# SHIELD_PROMINI.net
KiCad netlist of a schematic drawn in EAGLE
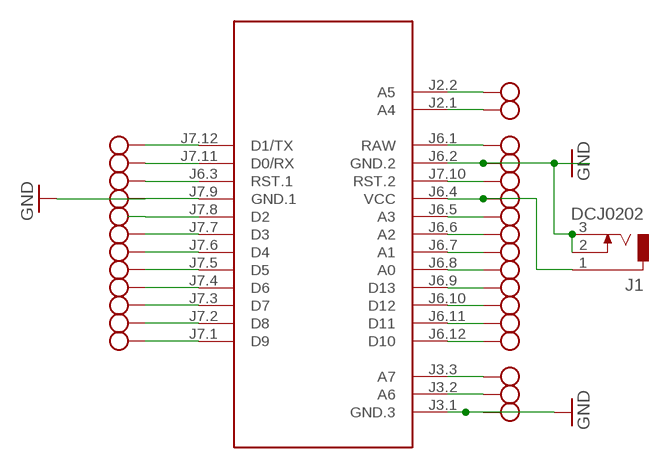
[diagram p0: schematic, sheet 1]

(export (version "E")
  (design (tool "Eeschema 10.0.6"))
  (components
    (comp (ref "J1")
      (value "DCJ0202")
      (footprint "eagle-import:DCJ0202")
      (libsource (lib "eagle-import") (part "DCJ0202"))
    )
    (comp (ref "M1")
      (value "ARDUINO-PRO-MINI-5.0V#NP")
      (footprint "eagle-import:ARDUINO-PRO-MINI#NP")
      (libsource (lib "eagle-import") (part "ARDUINO-PRO-MINI-#NP5.0V"))
    )
    (comp (ref "X1")
      (value "AK300/12")
      (footprint "eagle-import:AK300_12")
      (libsource (lib "eagle-import") (part "AK300/12"))
    )
    (comp (ref "X2")
      (value "AK300/12")
      (footprint "eagle-import:AK300_12")
      (libsource (lib "eagle-import") (part "AK300/12"))
    )
    (comp (ref "X3")
      (value "AK300/5")
      (footprint "eagle-import:AK300_5")
      (libsource (lib "eagle-import") (part "AK300/5"))
    )
  )
  (nets
    (net (code "1") (name "GND") (class "Default")
      (node (ref "J1") (pin "2") (pinfunction "2_2") (pintype "passive"))
      (node (ref "J1") (pin "3") (pinfunction "3_3") (pintype "passive"))
      (node (ref "M1") (pin "J3.1") (pinfunction "GND.3_J3.1") (pintype "bidirectional"))
      (node (ref "M1") (pin "J6.2") (pinfunction "GND.2_J6.2") (pintype "power_in"))
      (node (ref "M1") (pin "J7.9") (pinfunction "GND.1_J7.9") (pintype "power_in"))
      (node (ref "X1") (pin "9") (pinfunction "KL_9") (pintype "passive"))
      (node (ref "X2") (pin "2") (pinfunction "KL_2") (pintype "passive"))
      (node (ref "X3") (pin "3") (pinfunction "KL_3") (pintype "passive"))
    )
    (net (code "2") (name "Net-(M1-A0)") (class "Default")
      (node (ref "M1") (pin "J6.8") (pinfunction "A0_J6.8") (pintype "bidirectional"))
      (node (ref "X2") (pin "8") (pinfunction "KL_8") (pintype "passive"))
    )
    (net (code "3") (name "Net-(M1-A1)") (class "Default")
      (node (ref "M1") (pin "J6.7") (pinfunction "A1_J6.7") (pintype "bidirectional"))
      (node (ref "X2") (pin "7") (pinfunction "KL_7") (pintype "passive"))
    )
    (net (code "4") (name "Net-(M1-A2)") (class "Default")
      (node (ref "M1") (pin "J6.6") (pinfunction "A2_J6.6") (pintype "bidirectional"))
      (node (ref "X2") (pin "6") (pinfunction "KL_6") (pintype "passive"))
    )
    (net (code "5") (name "Net-(M1-A3)") (class "Default")
      (node (ref "M1") (pin "J6.5") (pinfunction "A3_J6.5") (pintype "bidirectional"))
      (node (ref "X2") (pin "5") (pinfunction "KL_5") (pintype "passive"))
    )
    (net (code "6") (name "Net-(M1-A4)") (class "Default")
      (node (ref "M1") (pin "J2.1") (pinfunction "A4_J2.1") (pintype "bidirectional"))
      (node (ref "X3") (pin "4") (pinfunction "KL_4") (pintype "passive"))
    )
    (net (code "7") (name "Net-(M1-A5)") (class "Default")
      (node (ref "M1") (pin "J2.2") (pinfunction "A5_J2.2") (pintype "bidirectional"))
      (node (ref "X3") (pin "5") (pinfunction "KL_5") (pintype "passive"))
    )
    (net (code "8") (name "Net-(M1-A6)") (class "Default")
      (node (ref "M1") (pin "J3.2") (pinfunction "A6_J3.2") (pintype "bidirectional"))
      (node (ref "X3") (pin "2") (pinfunction "KL_2") (pintype "passive"))
    )
    (net (code "9") (name "Net-(M1-A7)") (class "Default")
      (node (ref "M1") (pin "J3.3") (pinfunction "A7_J3.3") (pintype "bidirectional"))
      (node (ref "X3") (pin "1") (pinfunction "KL_1") (pintype "passive"))
    )
    (net (code "10") (name "Net-(M1-D0{slash}RX)") (class "Default")
      (node (ref "M1") (pin "J7.11") (pinfunction "D0/RX_J7.11") (pintype "bidirectional"))
      (node (ref "X1") (pin "11") (pinfunction "KL_11") (pintype "passive"))
    )
    (net (code "11") (name "Net-(M1-D1{slash}TX)") (class "Default")
      (node (ref "M1") (pin "J7.12") (pinfunction "D1/TX_J7.12") (pintype "bidirectional"))
      (node (ref "X1") (pin "12") (pinfunction "KL_12") (pintype "passive"))
    )
    (net (code "12") (name "Net-(M1-D2)") (class "Default")
      (node (ref "M1") (pin "J7.8") (pinfunction "D2_J7.8") (pintype "bidirectional"))
      (node (ref "X1") (pin "8") (pinfunction "KL_8") (pintype "passive"))
    )
    (net (code "13") (name "Net-(M1-D3)") (class "Default")
      (node (ref "M1") (pin "J7.7") (pinfunction "D3_J7.7") (pintype "bidirectional"))
      (node (ref "X1") (pin "7") (pinfunction "KL_7") (pintype "passive"))
    )
    (net (code "14") (name "Net-(M1-D4)") (class "Default")
      (node (ref "M1") (pin "J7.6") (pinfunction "D4_J7.6") (pintype "bidirectional"))
      (node (ref "X1") (pin "6") (pinfunction "KL_6") (pintype "passive"))
    )
    (net (code "15") (name "Net-(M1-D5)") (class "Default")
      (node (ref "M1") (pin "J7.5") (pinfunction "D5_J7.5") (pintype "bidirectional"))
      (node (ref "X1") (pin "5") (pinfunction "KL_5") (pintype "passive"))
    )
    (net (code "16") (name "Net-(M1-D6)") (class "Default")
      (node (ref "M1") (pin "J7.4") (pinfunction "D6_J7.4") (pintype "bidirectional"))
      (node (ref "X1") (pin "4") (pinfunction "KL_4") (pintype "passive"))
    )
    (net (code "17") (name "Net-(M1-D7)") (class "Default")
      (node (ref "M1") (pin "J7.3") (pinfunction "D7_J7.3") (pintype "bidirectional"))
      (node (ref "X1") (pin "3") (pinfunction "KL_3") (pintype "passive"))
    )
    (net (code "18") (name "Net-(M1-D8)") (class "Default")
      (node (ref "M1") (pin "J7.2") (pinfunction "D8_J7.2") (pintype "bidirectional"))
      (node (ref "X1") (pin "2") (pinfunction "KL_2") (pintype "passive"))
    )
    (net (code "19") (name "Net-(M1-D9)") (class "Default")
      (node (ref "M1") (pin "J7.1") (pinfunction "D9_J7.1") (pintype "bidirectional"))
      (node (ref "X1") (pin "1") (pinfunction "KL_1") (pintype "passive"))
    )
    (net (code "20") (name "Net-(M1-D10)") (class "Default")
      (node (ref "M1") (pin "J6.12") (pinfunction "D10_J6.12") (pintype "bidirectional"))
      (node (ref "X2") (pin "12") (pinfunction "KL_12") (pintype "passive"))
    )
    (net (code "21") (name "Net-(M1-D11)") (class "Default")
      (node (ref "M1") (pin "J6.11") (pinfunction "D11_J6.11") (pintype "bidirectional"))
      (node (ref "X2") (pin "11") (pinfunction "KL_11") (pintype "passive"))
    )
    (net (code "22") (name "Net-(M1-D12)") (class "Default")
      (node (ref "M1") (pin "J6.10") (pinfunction "D12_J6.10") (pintype "bidirectional"))
      (node (ref "X2") (pin "10") (pinfunction "KL_10") (pintype "passive"))
    )
    (net (code "23") (name "Net-(M1-D13)") (class "Default")
      (node (ref "M1") (pin "J6.9") (pinfunction "D13_J6.9") (pintype "bidirectional"))
      (node (ref "X2") (pin "9") (pinfunction "KL_9") (pintype "passive"))
    )
    (net (code "24") (name "Net-(M1-RAW)") (class "Default")
      (node (ref "M1") (pin "J6.1") (pinfunction "RAW_J6.1") (pintype "power_in"))
      (node (ref "X2") (pin "1") (pinfunction "KL_1") (pintype "passive"))
    )
    (net (code "25") (name "Net-(M1-RST.1)") (class "Default")
      (node (ref "M1") (pin "J6.3") (pinfunction "RST.1_J6.3") (pintype "bidirectional"))
      (node (ref "X2") (pin "3") (pinfunction "KL_3") (pintype "passive"))
    )
    (net (code "26") (name "Net-(M1-RST.2)") (class "Default")
      (node (ref "M1") (pin "J7.10") (pinfunction "RST.2_J7.10") (pintype "bidirectional"))
      (node (ref "X1") (pin "10") (pinfunction "KL_10") (pintype "passive"))
    )
    (net (code "27") (name "Net-(M1-VCC)") (class "Default")
      (node (ref "J1") (pin "1") (pinfunction "1_1") (pintype "passive"))
      (node (ref "M1") (pin "J6.4") (pinfunction "VCC_J6.4") (pintype "power_in"))
      (node (ref "X2") (pin "4") (pinfunction "KL_4") (pintype "passive"))
    )
  )
)
